# PLP-250.net
KiCad netlist of a schematic drawn in EAGLE
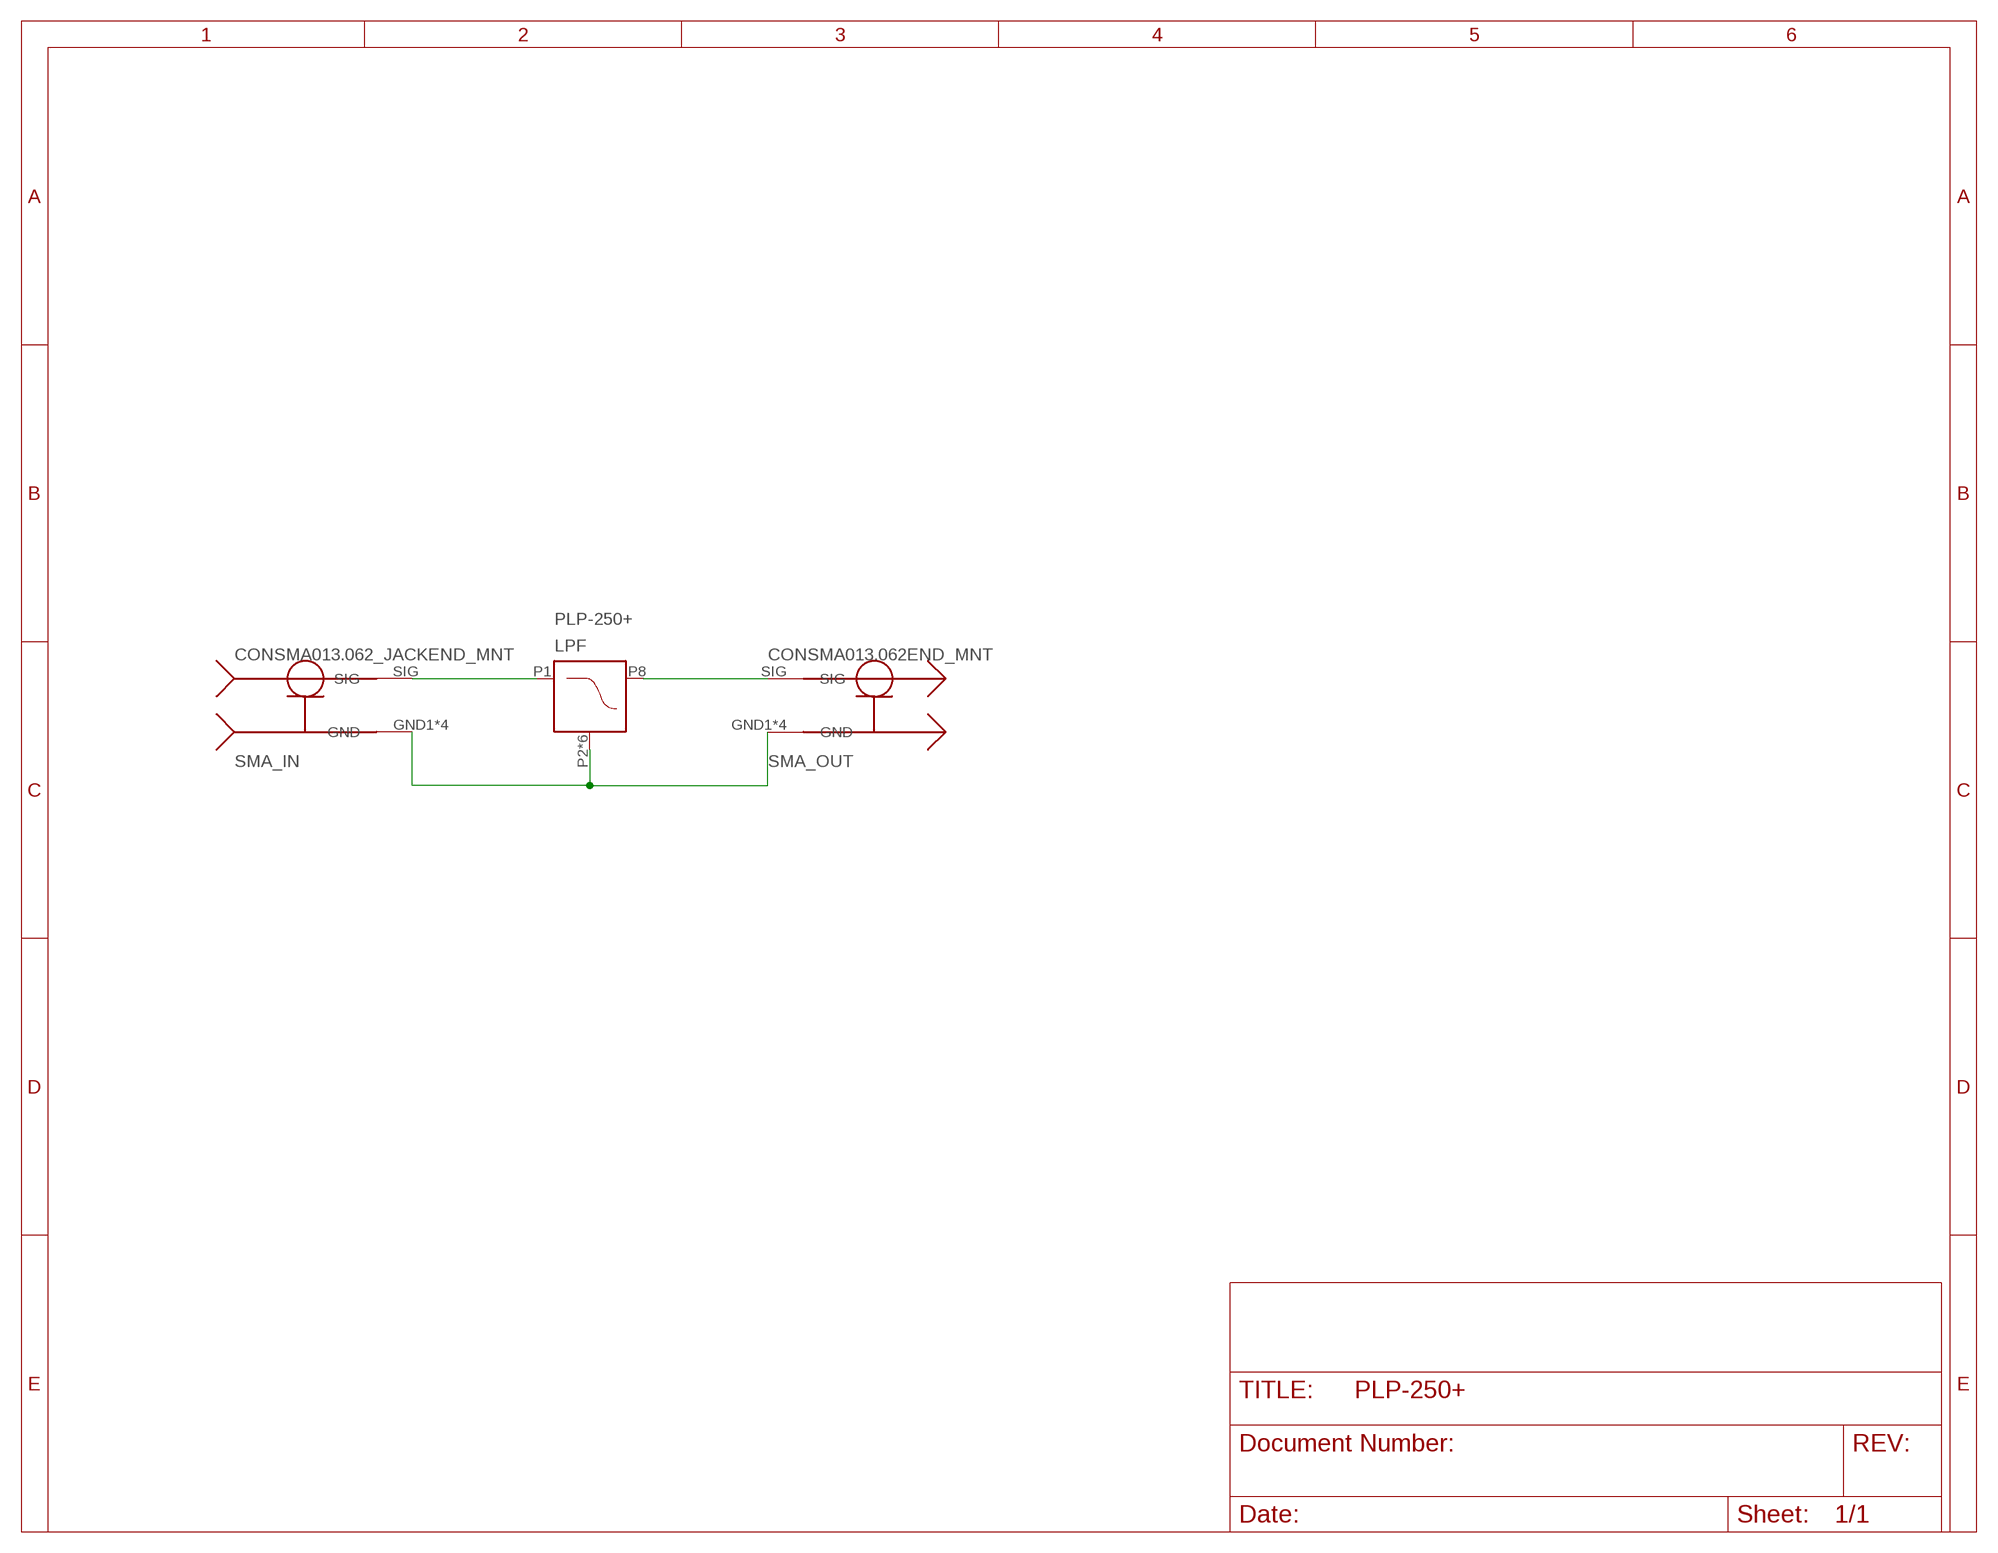
[diagram p0: schematic, sheet 1]

(export (version "E")
  (design (tool "Eeschema 10.0.6"))
  (components
    (comp (ref "LPF")
      (value "PLP-250+")
      (footprint "eagle-import:A01")
      (libsource (lib "eagle-import") (part "PLP-250+"))
    )
    (comp (ref "SMA_IN")
      (value "CONSMA013.062_JACKEND_MNT")
      (footprint "eagle-import:SMA_EDGE_MNT")
      (libsource (lib "eagle-import") (part "CONSMA013.062_JACKEND_MNT"))
    )
    (comp (ref "SMA_OUT")
      (value "CONSMA013.062END_MNT")
      (footprint "eagle-import:SMA_EDGE_MNT")
      (libsource (lib "eagle-import") (part "CONSMA013.062END_MNT"))
    )
  )
  (nets
    (net (code "1") (name "Net-(LPF-GND-PadP2)") (class "Default")
      (node (ref "LPF") (pin "P2") (pinfunction "GND_P2") (pintype "bidirectional"))
      (node (ref "LPF") (pin "P3") (pinfunction "GND_P3") (pintype "bidirectional"))
      (node (ref "LPF") (pin "P4") (pinfunction "GND_P4") (pintype "bidirectional"))
      (node (ref "LPF") (pin "P5") (pinfunction "GND_P5") (pintype "bidirectional"))
      (node (ref "LPF") (pin "P6") (pinfunction "GND_P6") (pintype "bidirectional"))
      (node (ref "LPF") (pin "P7") (pinfunction "GND_P7") (pintype "bidirectional"))
      (node (ref "SMA_IN") (pin "GND1") (pinfunction "GND_GND1") (pintype "bidirectional"))
      (node (ref "SMA_IN") (pin "GND2") (pinfunction "GND_GND2") (pintype "bidirectional"))
      (node (ref "SMA_IN") (pin "GND3") (pinfunction "GND_GND3") (pintype "bidirectional"))
      (node (ref "SMA_IN") (pin "GND4") (pinfunction "GND_GND4") (pintype "bidirectional"))
      (node (ref "SMA_OUT") (pin "GND1") (pinfunction "GND_GND1") (pintype "bidirectional"))
      (node (ref "SMA_OUT") (pin "GND2") (pinfunction "GND_GND2") (pintype "bidirectional"))
      (node (ref "SMA_OUT") (pin "GND3") (pinfunction "GND_GND3") (pintype "bidirectional"))
      (node (ref "SMA_OUT") (pin "GND4") (pinfunction "GND_GND4") (pintype "bidirectional"))
    )
    (net (code "2") (name "Net-(LPF-RF_IN)") (class "Default")
      (node (ref "LPF") (pin "P1") (pinfunction "RF_IN_P1") (pintype "input"))
      (node (ref "SMA_IN") (pin "SIG") (pinfunction "SIG_SIG") (pintype "bidirectional"))
    )
    (net (code "3") (name "Net-(LPF-RF_OUT)") (class "Default")
      (node (ref "LPF") (pin "P8") (pinfunction "RF_OUT_P8") (pintype "output"))
      (node (ref "SMA_OUT") (pin "SIG") (pinfunction "SIG_SIG") (pintype "bidirectional"))
    )
  )
)
